# Tlcd-43.net
KiCad netlist of a schematic drawn in Altium Designer
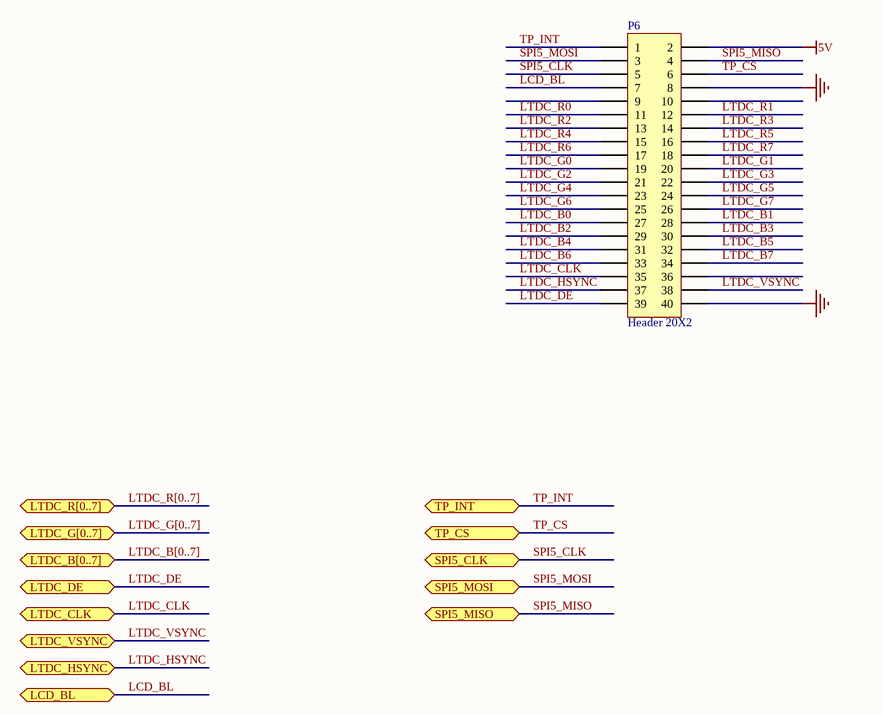
[diagram p0: Tlcd-43.SchDoc]

(export (version "E")
  (design (tool "Eeschema 10.0.6"))
  (components
    (comp (ref "P6")
      (value "Header 20X2")
      (footprint "HDR2X20")
      (description "Header, 20-Pin, Dual row")
      (libsource (lib "Core429IBaseBoard") (part "Header 20X2"))
    )
  )
  (nets
    (net (code "1") (name "/LCD_BL") (class "Default")
      (node (ref "P6") (pin "7") (pinfunction "7_7") (pintype "passive"))
    )
    (net (code "2") (name "/LTDC_B0") (class "Default")
      (node (ref "P6") (pin "27") (pinfunction "27_27") (pintype "passive"))
    )
    (net (code "3") (name "/LTDC_B1") (class "Default")
      (node (ref "P6") (pin "28") (pinfunction "28_28") (pintype "passive"))
    )
    (net (code "4") (name "/LTDC_B2") (class "Default")
      (node (ref "P6") (pin "29") (pinfunction "29_29") (pintype "passive"))
    )
    (net (code "5") (name "/LTDC_B3") (class "Default")
      (node (ref "P6") (pin "30") (pinfunction "30_30") (pintype "passive"))
    )
    (net (code "6") (name "/LTDC_B4") (class "Default")
      (node (ref "P6") (pin "31") (pinfunction "31_31") (pintype "passive"))
    )
    (net (code "7") (name "/LTDC_B5") (class "Default")
      (node (ref "P6") (pin "32") (pinfunction "32_32") (pintype "passive"))
    )
    (net (code "8") (name "/LTDC_B6") (class "Default")
      (node (ref "P6") (pin "33") (pinfunction "33_33") (pintype "passive"))
    )
    (net (code "9") (name "/LTDC_B7") (class "Default")
      (node (ref "P6") (pin "34") (pinfunction "34_34") (pintype "passive"))
    )
    (net (code "11") (name "/LTDC_CLK") (class "Default")
      (node (ref "P6") (pin "35") (pinfunction "35_35") (pintype "passive"))
    )
    (net (code "12") (name "/LTDC_DE") (class "Default")
      (node (ref "P6") (pin "39") (pinfunction "39_39") (pintype "passive"))
    )
    (net (code "13") (name "/LTDC_G0") (class "Default")
      (node (ref "P6") (pin "19") (pinfunction "19_19") (pintype "passive"))
    )
    (net (code "14") (name "/LTDC_G1") (class "Default")
      (node (ref "P6") (pin "20") (pinfunction "20_20") (pintype "passive"))
    )
    (net (code "15") (name "/LTDC_G2") (class "Default")
      (node (ref "P6") (pin "21") (pinfunction "21_21") (pintype "passive"))
    )
    (net (code "16") (name "/LTDC_G3") (class "Default")
      (node (ref "P6") (pin "22") (pinfunction "22_22") (pintype "passive"))
    )
    (net (code "17") (name "/LTDC_G4") (class "Default")
      (node (ref "P6") (pin "23") (pinfunction "23_23") (pintype "passive"))
    )
    (net (code "18") (name "/LTDC_G5") (class "Default")
      (node (ref "P6") (pin "24") (pinfunction "24_24") (pintype "passive"))
    )
    (net (code "19") (name "/LTDC_G6") (class "Default")
      (node (ref "P6") (pin "25") (pinfunction "25_25") (pintype "passive"))
    )
    (net (code "20") (name "/LTDC_G7") (class "Default")
      (node (ref "P6") (pin "26") (pinfunction "26_26") (pintype "passive"))
    )
    (net (code "22") (name "/LTDC_HSYNC") (class "Default")
      (node (ref "P6") (pin "37") (pinfunction "37_37") (pintype "passive"))
    )
    (net (code "23") (name "/LTDC_R0") (class "Default")
      (node (ref "P6") (pin "11") (pinfunction "11_11") (pintype "passive"))
    )
    (net (code "24") (name "/LTDC_R1") (class "Default")
      (node (ref "P6") (pin "12") (pinfunction "12_12") (pintype "passive"))
    )
    (net (code "25") (name "/LTDC_R2") (class "Default")
      (node (ref "P6") (pin "13") (pinfunction "13_13") (pintype "passive"))
    )
    (net (code "26") (name "/LTDC_R3") (class "Default")
      (node (ref "P6") (pin "14") (pinfunction "14_14") (pintype "passive"))
    )
    (net (code "27") (name "/LTDC_R4") (class "Default")
      (node (ref "P6") (pin "15") (pinfunction "15_15") (pintype "passive"))
    )
    (net (code "28") (name "/LTDC_R5") (class "Default")
      (node (ref "P6") (pin "16") (pinfunction "16_16") (pintype "passive"))
    )
    (net (code "29") (name "/LTDC_R6") (class "Default")
      (node (ref "P6") (pin "17") (pinfunction "17_17") (pintype "passive"))
    )
    (net (code "30") (name "/LTDC_R7") (class "Default")
      (node (ref "P6") (pin "18") (pinfunction "18_18") (pintype "passive"))
    )
    (net (code "32") (name "/LTDC_VSYNC") (class "Default")
      (node (ref "P6") (pin "38") (pinfunction "38_38") (pintype "passive"))
    )
    (net (code "33") (name "/SPI5_CLK") (class "Default")
      (node (ref "P6") (pin "5") (pinfunction "5_5") (pintype "passive"))
    )
    (net (code "34") (name "/SPI5_MISO") (class "Default")
      (node (ref "P6") (pin "4") (pinfunction "4_4") (pintype "passive"))
    )
    (net (code "35") (name "/SPI5_MOSI") (class "Default")
      (node (ref "P6") (pin "3") (pinfunction "3_3") (pintype "passive"))
    )
    (net (code "36") (name "/TP_CS") (class "Default")
      (node (ref "P6") (pin "6") (pinfunction "6_6") (pintype "passive"))
    )
    (net (code "37") (name "/TP_INT") (class "Default")
      (node (ref "P6") (pin "1") (pinfunction "1_1") (pintype "passive"))
    )
    (net (code "38") (name "5V") (class "Default")
      (node (ref "P6") (pin "2") (pinfunction "2_2") (pintype "passive"))
    )
    (net (code "39") (name "DGND") (class "Default")
      (node (ref "P6") (pin "40") (pinfunction "40_40") (pintype "passive"))
      (node (ref "P6") (pin "8") (pinfunction "8_8") (pintype "passive"))
    )
    (net (code "40") (name "unconnected-(P6-Pad9)") (class "Default")
      (node (ref "P6") (pin "9") (pinfunction "9_9") (pintype "passive"))
    )
    (net (code "41") (name "unconnected-(P6-Pad10)") (class "Default")
      (node (ref "P6") (pin "10") (pinfunction "10_10") (pintype "passive"))
    )
    (net (code "42") (name "unconnected-(P6-Pad36)") (class "Default")
      (node (ref "P6") (pin "36") (pinfunction "36_36") (pintype "passive"))
    )
  )
)
